# Microcontroller.net
KiCad netlist of a schematic drawn in Altium Designer
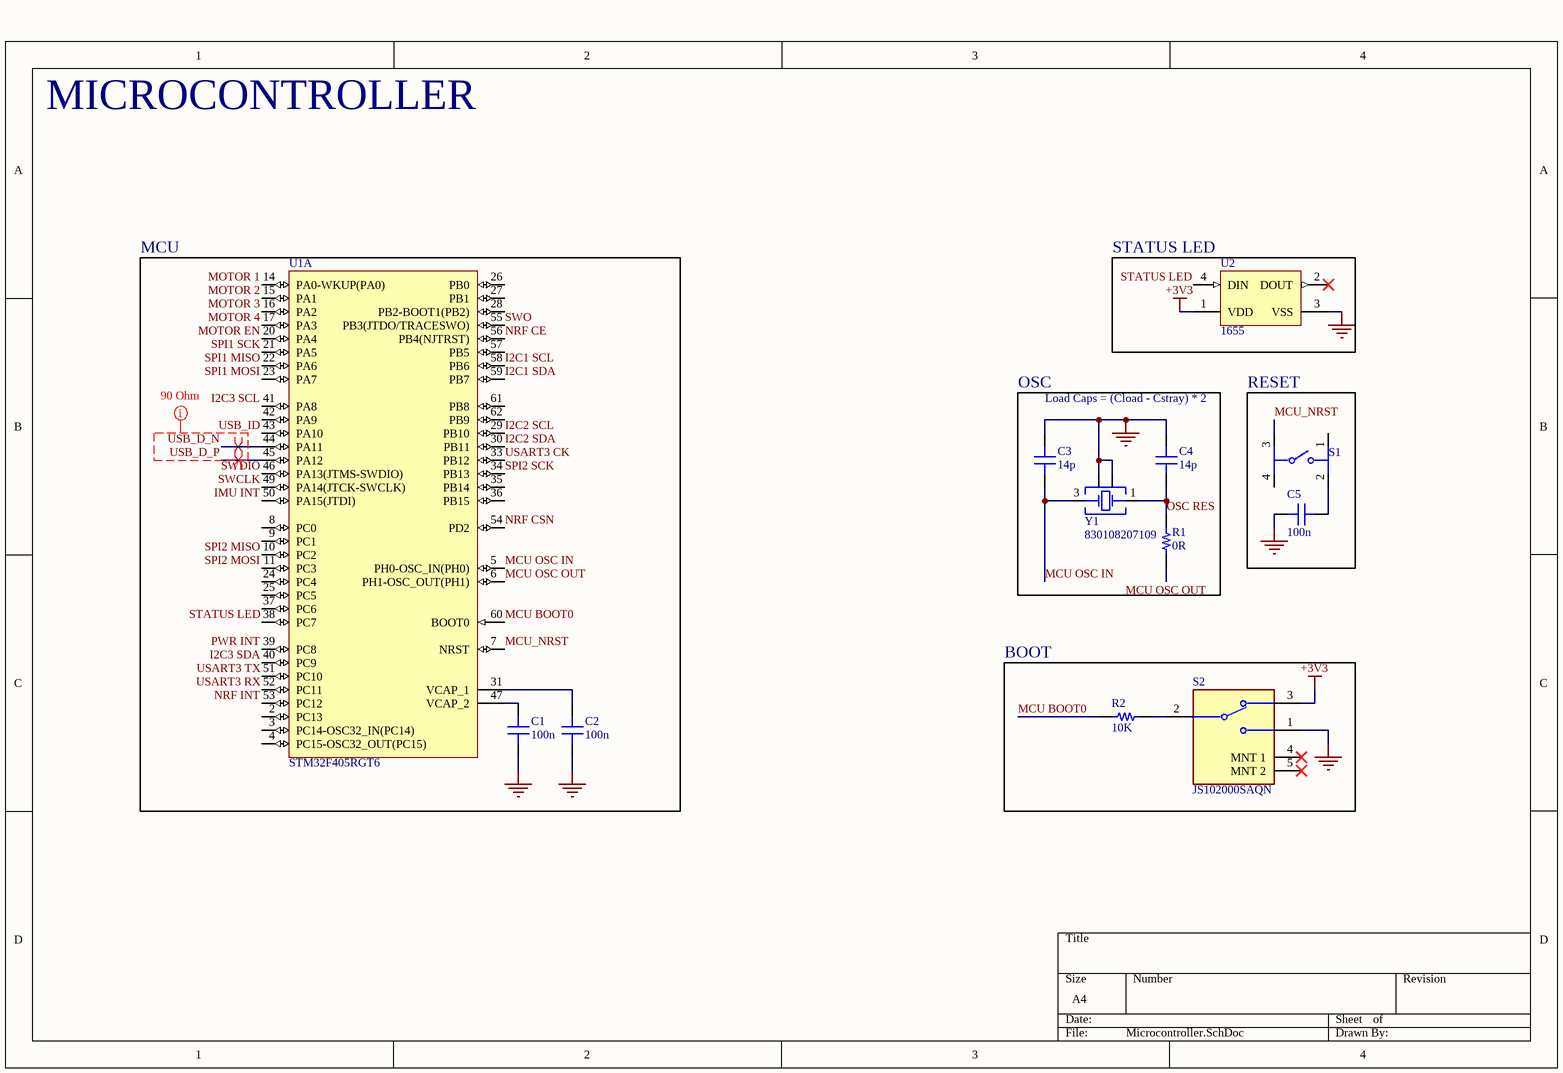
[diagram p0: Microcontroller.SchDoc]

(export (version "E")
  (design (tool "Eeschema 10.0.6"))
  (components
    (comp (ref "C1")
      (value "100n")
      (footprint "CAP 0402_1005")
      (description "CAP CER 100NF 10V X7R 0402")
      (fields
        (field (name "PART NUMBER") "CL05B104KP5VPNC")
        (field (name "MANUFACTURER") "Samsung Electro-Mechanics")
      )
      (libsource (lib "Celestial Altium Library - altium_library") (part "Capacitor"))
    )
    (comp (ref "C2")
      (value "100n")
      (footprint "CAP 0402_1005")
      (description "CAP CER 100NF 10V X7R 0402")
      (fields
        (field (name "PART NUMBER") "CL05B104KP5VPNC")
        (field (name "MANUFACTURER") "Samsung Electro-Mechanics")
      )
      (libsource (lib "Celestial Altium Library - altium_library") (part "Capacitor"))
    )
    (comp (ref "C3")
      (value "14p")
      (footprint "CAP 0402_1005")
      (description "CAP CER 14PF 50V C0G/NP0 0402")
      (fields (field (name "PART NUMBER") "GJM1555C1H140GB01D"))
      (libsource (lib "Celestial Altium Library - altium_library") (part "Capacitor"))
    )
    (comp (ref "C4")
      (value "14p")
      (footprint "CAP 0402_1005")
      (description "CAP CER 14PF 50V C0G/NP0 0402")
      (fields (field (name "PART NUMBER") "GJM1555C1H140GB01D"))
      (libsource (lib "Celestial Altium Library - altium_library") (part "Capacitor"))
    )
    (comp (ref "C5")
      (value "100n")
      (footprint "CAP 0402_1005")
      (description "CAP CER 100NF 10V X7R 0402")
      (fields (field (name "PART NUMBER") "CL05B104KP5VPNC"))
      (libsource (lib "Celestial Altium Library - altium_library") (part "Capacitor"))
    )
    (comp (ref "R1")
      (value "0R")
      (footprint "RES 0402_1005")
      (description "0402 JUMPER ON TAPE AND REEL")
      (fields (field (name "PART NUMBER") "5112"))
      (libsource (lib "Celestial Altium Library - altium_library") (part "Resistor"))
    )
    (comp (ref "R2")
      (value "10K")
      (footprint "RES 0402_1005")
      (description "RES 10K OHM 0.1% 1/10W 0402")
      (fields (field (name "PART NUMBER") "RP73PF1E10KBTD"))
      (libsource (lib "Celestial Altium Library - altium_library") (part "Resistor"))
    )
    (comp (ref "S1")
      (value "PTS645SM43SMTR92LFS")
      (footprint "FP-PTS645SM43SMTR92LFS-MFG")
      (description "SWITCH TACTILE SPST-NO 0.05A 12V")
      (libsource (lib "Altium Content Vault") (part "1adf0dd01260c80cf25a44bfd6b99ba"))
    )
    (comp (ref "S2")
      (value "JS102000SAQN")
      (footprint "FP-JS102000SAQN-MFG")
      (description "SWITCH SLIDE SPDT 1MA 5V")
      (libsource (lib "Altium Content Vault") (part "6887e5fe807d9c5c2853bed39bc55bf"))
    )
    (comp (ref "U1")
      (value "STM32F405RGT6")
      (footprint "STM-LQFP64_M")
      (fields (field (name "MANUFACTURER") "STMicroelectronics"))
      (libsource (lib "Altium Content Vault") (part "MC-ARM-STM32F4X5-SQ64"))
    )
    (comp (ref "U2")
      (value "1655")
      (footprint "ADA-RGB-1655_V")
      (fields (field (name "MANUFACTURER") "Adafruit-Industries-LLC"))
      (libsource (lib "Altium Content Vault") (part "ADA-RGB-1655-4"))
    )
    (comp (ref "Y1")
      (value "830108207109")
      (footprint "WE-XTAL_CFPX-180")
      (description "830108207109 WE-XTAL Quartz Crystal")
      (libsource (lib "Altium Content Vault") (part "WE-XTAL_CFPX-180"))
    )
  )
  (nets
    (net (code "1") (name "+3V3") (class "Default")
      (node (ref "S2") (pin "3") (pinfunction "3_3") (pintype "passive"))
      (node (ref "U2") (pin "1") (pinfunction "VDD_1") (pintype "power_in"))
    )
    (net (code "2") (name "/I2C1 SCL") (class "Default")
      (node (ref "U1") (pin "58") (pinfunction "PB6_58") (pintype "bidirectional"))
    )
    (net (code "3") (name "/I2C1 SDA") (class "Default")
      (node (ref "U1") (pin "59") (pinfunction "PB7_59") (pintype "bidirectional"))
    )
    (net (code "4") (name "/I2C2 SCL") (class "Default")
      (node (ref "U1") (pin "29") (pinfunction "PB10_29") (pintype "bidirectional"))
    )
    (net (code "5") (name "/I2C2 SDA") (class "Default")
      (node (ref "U1") (pin "30") (pinfunction "PB11_30") (pintype "bidirectional"))
    )
    (net (code "6") (name "/I2C3 SCL") (class "Default")
      (node (ref "U1") (pin "41") (pinfunction "PA8_41") (pintype "bidirectional"))
    )
    (net (code "7") (name "/I2C3 SDA") (class "Default")
      (node (ref "U1") (pin "40") (pinfunction "PC9_40") (pintype "bidirectional"))
    )
    (net (code "8") (name "/IMU INT") (class "Default")
      (node (ref "U1") (pin "50") (pinfunction "PA15(JTDI)_50") (pintype "bidirectional"))
    )
    (net (code "9") (name "/MCU BOOT0") (class "Default")
      (node (ref "R2") (pin "1") (pinfunction "1_1") (pintype "passive"))
      (node (ref "U1") (pin "60") (pinfunction "BOOT0_60") (pintype "input"))
    )
    (net (code "10") (name "/MCU OSC IN") (class "Default")
      (node (ref "C3") (pin "1") (pinfunction "1_1") (pintype "passive"))
      (node (ref "U1") (pin "5") (pinfunction "PH0-OSC_IN(PH0)_5") (pintype "bidirectional"))
      (node (ref "Y1") (pin "3") (pinfunction "Crystal_3") (pintype "passive"))
    )
    (net (code "11") (name "/MCU OSC OUT") (class "Default")
      (node (ref "R1") (pin "1") (pinfunction "1_1") (pintype "passive"))
      (node (ref "U1") (pin "6") (pinfunction "PH1-OSC_OUT(PH1)_6") (pintype "bidirectional"))
    )
    (net (code "12") (name "/MCU_NRST") (class "Default")
      (node (ref "S1") (pin "3") (pinfunction "3_3") (pintype "passive"))
      (node (ref "U1") (pin "7") (pinfunction "NRST_7") (pintype "bidirectional"))
    )
    (net (code "13") (name "/MOTOR 1") (class "Default")
      (node (ref "U1") (pin "14") (pinfunction "PA0-WKUP(PA0)_14") (pintype "bidirectional"))
    )
    (net (code "14") (name "/MOTOR 2") (class "Default")
      (node (ref "U1") (pin "15") (pinfunction "PA1_15") (pintype "bidirectional"))
    )
    (net (code "15") (name "/MOTOR 3") (class "Default")
      (node (ref "U1") (pin "16") (pinfunction "PA2_16") (pintype "bidirectional"))
    )
    (net (code "16") (name "/MOTOR 4") (class "Default")
      (node (ref "U1") (pin "17") (pinfunction "PA3_17") (pintype "bidirectional"))
    )
    (net (code "17") (name "/MOTOR EN") (class "Default")
      (node (ref "U1") (pin "20") (pinfunction "PA4_20") (pintype "bidirectional"))
    )
    (net (code "18") (name "/NRF CE") (class "Default")
      (node (ref "U1") (pin "56") (pinfunction "PB4(NJTRST)_56") (pintype "bidirectional"))
    )
    (net (code "19") (name "/NRF CSN") (class "Default")
      (node (ref "U1") (pin "54") (pinfunction "PD2_54") (pintype "bidirectional"))
    )
    (net (code "20") (name "/NRF INT") (class "Default")
      (node (ref "U1") (pin "53") (pinfunction "PC12_53") (pintype "bidirectional"))
    )
    (net (code "21") (name "/OSC RES") (class "Default")
      (node (ref "C4") (pin "1") (pinfunction "1_1") (pintype "passive"))
      (node (ref "R1") (pin "2") (pinfunction "2_2") (pintype "passive"))
      (node (ref "Y1") (pin "1") (pinfunction "Crystal_1") (pintype "passive"))
    )
    (net (code "22") (name "/PWR INT") (class "Default")
      (node (ref "U1") (pin "39") (pinfunction "PC8_39") (pintype "bidirectional"))
    )
    (net (code "23") (name "/SPI1 MISO") (class "Default")
      (node (ref "U1") (pin "22") (pinfunction "PA6_22") (pintype "bidirectional"))
    )
    (net (code "24") (name "/SPI1 MOSI") (class "Default")
      (node (ref "U1") (pin "23") (pinfunction "PA7_23") (pintype "bidirectional"))
    )
    (net (code "25") (name "/SPI1 SCK") (class "Default")
      (node (ref "U1") (pin "21") (pinfunction "PA5_21") (pintype "bidirectional"))
    )
    (net (code "26") (name "/SPI2 MISO") (class "Default")
      (node (ref "U1") (pin "10") (pinfunction "PC2_10") (pintype "bidirectional"))
    )
    (net (code "27") (name "/SPI2 MOSI") (class "Default")
      (node (ref "U1") (pin "11") (pinfunction "PC3_11") (pintype "bidirectional"))
    )
    (net (code "28") (name "/SPI2 SCK") (class "Default")
      (node (ref "U1") (pin "34") (pinfunction "PB13_34") (pintype "bidirectional"))
    )
    (net (code "29") (name "/STATUS LED") (class "Default")
      (node (ref "U1") (pin "38") (pinfunction "PC7_38") (pintype "bidirectional"))
      (node (ref "U2") (pin "4") (pinfunction "DIN_4") (pintype "input"))
    )
    (net (code "30") (name "/SWCLK") (class "Default")
      (node (ref "U1") (pin "49") (pinfunction "PA14(JTCK-SWCLK)_49") (pintype "bidirectional"))
    )
    (net (code "31") (name "/SWDIO") (class "Default")
      (node (ref "U1") (pin "46") (pinfunction "PA13(JTMS-SWDIO)_46") (pintype "bidirectional"))
    )
    (net (code "32") (name "/SWO") (class "Default")
      (node (ref "U1") (pin "55") (pinfunction "PB3(JTDO/TRACESWO)_55") (pintype "bidirectional"))
    )
    (net (code "33") (name "/USART3 CK") (class "Default")
      (node (ref "U1") (pin "33") (pinfunction "PB12_33") (pintype "bidirectional"))
    )
    (net (code "34") (name "/USART3 RX") (class "Default")
      (node (ref "U1") (pin "52") (pinfunction "PC11_52") (pintype "bidirectional"))
    )
    (net (code "35") (name "/USART3 TX") (class "Default")
      (node (ref "U1") (pin "51") (pinfunction "PC10_51") (pintype "bidirectional"))
    )
    (net (code "36") (name "/USB_D_N") (class "Default")
      (node (ref "U1") (pin "44") (pinfunction "PA11_44") (pintype "bidirectional"))
    )
    (net (code "37") (name "/USB_D_P") (class "Default")
      (node (ref "U1") (pin "45") (pinfunction "PA12_45") (pintype "bidirectional"))
    )
    (net (code "38") (name "/USB_ID") (class "Default")
      (node (ref "U1") (pin "43") (pinfunction "PA10_43") (pintype "bidirectional"))
    )
    (net (code "39") (name "GND") (class "Default")
      (node (ref "C1") (pin "1") (pinfunction "1_1") (pintype "passive"))
      (node (ref "C2") (pin "1") (pinfunction "1_1") (pintype "passive"))
      (node (ref "C3") (pin "2") (pinfunction "2_2") (pintype "passive"))
      (node (ref "C4") (pin "2") (pinfunction "2_2") (pintype "passive"))
      (node (ref "C5") (pin "2") (pinfunction "2_2") (pintype "passive"))
      (node (ref "S2") (pin "1") (pinfunction "1_1") (pintype "passive"))
      (node (ref "U2") (pin "3") (pinfunction "VSS_3") (pintype "power_in"))
      (node (ref "Y1") (pin "2") (pinfunction "GND&Lid_2") (pintype "passive"))
      (node (ref "Y1") (pin "4") (pinfunction "GND&Lid_4") (pintype "passive"))
    )
    (net (code "40") (name "Net-(C5-Pad1)") (class "Default")
      (node (ref "C5") (pin "1") (pinfunction "1_1") (pintype "passive"))
      (node (ref "S1") (pin "2") (pinfunction "2_2") (pintype "passive"))
    )
    (net (code "41") (name "Net-(S2-C)") (class "Default")
      (node (ref "R2") (pin "2") (pinfunction "2_2") (pintype "passive"))
      (node (ref "S2") (pin "2") (pinfunction "C_2") (pintype "passive"))
    )
    (net (code "42") (name "Net-(U1A-VCAP_1)") (class "Default")
      (node (ref "C2") (pin "2") (pinfunction "2_2") (pintype "passive"))
      (node (ref "U1") (pin "31") (pinfunction "VCAP_1_31") (pintype "power_in"))
    )
    (net (code "43") (name "Net-(U1A-VCAP_2)") (class "Default")
      (node (ref "C1") (pin "2") (pinfunction "2_2") (pintype "passive"))
      (node (ref "U1") (pin "47") (pinfunction "VCAP_2_47") (pintype "power_in"))
    )
    (net (code "44") (name "unconnected-(S1-Pad1)") (class "Default")
      (node (ref "S1") (pin "1") (pinfunction "1_1") (pintype "passive"))
    )
    (net (code "45") (name "unconnected-(S1-Pad4)") (class "Default")
      (node (ref "S1") (pin "4") (pinfunction "4_4") (pintype "passive"))
    )
    (net (code "46") (name "unconnected-(S2-MNT_1-Pad4)") (class "Default")
      (node (ref "S2") (pin "4") (pinfunction "MNT_1_4") (pintype "passive+no_connect"))
    )
    (net (code "47") (name "unconnected-(S2-MNT_2-Pad5)") (class "Default")
      (node (ref "S2") (pin "5") (pinfunction "MNT_2_5") (pintype "passive+no_connect"))
    )
    (net (code "48") (name "unconnected-(U1A-PA9-Pad42)") (class "Default")
      (node (ref "U1") (pin "42") (pinfunction "PA9_42") (pintype "bidirectional"))
    )
    (net (code "49") (name "unconnected-(U1A-PB0-Pad26)") (class "Default")
      (node (ref "U1") (pin "26") (pinfunction "PB0_26") (pintype "bidirectional"))
    )
    (net (code "50") (name "unconnected-(U1A-PB1-Pad27)") (class "Default")
      (node (ref "U1") (pin "27") (pinfunction "PB1_27") (pintype "bidirectional"))
    )
    (net (code "51") (name "unconnected-(U1A-PB2-BOOT1(PB2)-Pad28)") (class "Default")
      (node (ref "U1") (pin "28") (pinfunction "PB2-BOOT1(PB2)_28") (pintype "bidirectional"))
    )
    (net (code "52") (name "unconnected-(U1A-PB5-Pad57)") (class "Default")
      (node (ref "U1") (pin "57") (pinfunction "PB5_57") (pintype "bidirectional"))
    )
    (net (code "53") (name "unconnected-(U1A-PB8-Pad61)") (class "Default")
      (node (ref "U1") (pin "61") (pinfunction "PB8_61") (pintype "bidirectional"))
    )
    (net (code "54") (name "unconnected-(U1A-PB9-Pad62)") (class "Default")
      (node (ref "U1") (pin "62") (pinfunction "PB9_62") (pintype "bidirectional"))
    )
    (net (code "55") (name "unconnected-(U1A-PB14-Pad35)") (class "Default")
      (node (ref "U1") (pin "35") (pinfunction "PB14_35") (pintype "bidirectional"))
    )
    (net (code "56") (name "unconnected-(U1A-PB15-Pad36)") (class "Default")
      (node (ref "U1") (pin "36") (pinfunction "PB15_36") (pintype "bidirectional"))
    )
    (net (code "57") (name "unconnected-(U1A-PC0-Pad8)") (class "Default")
      (node (ref "U1") (pin "8") (pinfunction "PC0_8") (pintype "bidirectional"))
    )
    (net (code "58") (name "unconnected-(U1A-PC1-Pad9)") (class "Default")
      (node (ref "U1") (pin "9") (pinfunction "PC1_9") (pintype "bidirectional"))
    )
    (net (code "59") (name "unconnected-(U1A-PC4-Pad24)") (class "Default")
      (node (ref "U1") (pin "24") (pinfunction "PC4_24") (pintype "bidirectional"))
    )
    (net (code "60") (name "unconnected-(U1A-PC5-Pad25)") (class "Default")
      (node (ref "U1") (pin "25") (pinfunction "PC5_25") (pintype "bidirectional"))
    )
    (net (code "61") (name "unconnected-(U1A-PC6-Pad37)") (class "Default")
      (node (ref "U1") (pin "37") (pinfunction "PC6_37") (pintype "bidirectional"))
    )
    (net (code "62") (name "unconnected-(U1A-PC13-Pad2)") (class "Default")
      (node (ref "U1") (pin "2") (pinfunction "PC13_2") (pintype "bidirectional"))
    )
    (net (code "63") (name "unconnected-(U1A-PC14-OSC32_IN(PC14)-Pad3)") (class "Default")
      (node (ref "U1") (pin "3") (pinfunction "PC14-OSC32_IN(PC14)_3") (pintype "bidirectional"))
    )
    (net (code "64") (name "unconnected-(U1A-PC15-OSC32_OUT(PC15)-Pad4)") (class "Default")
      (node (ref "U1") (pin "4") (pinfunction "PC15-OSC32_OUT(PC15)_4") (pintype "bidirectional"))
    )
    (net (code "65") (name "unconnected-(U2-DOUT-Pad2)") (class "Default")
      (node (ref "U2") (pin "2") (pinfunction "DOUT_2") (pintype "output+no_connect"))
    )
  )
)
